# multiple_LED.net
KiCad netlist of a schematic drawn in EAGLE
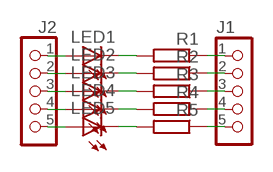
[diagram p0: schematic, sheet 1]

(export (version "E")
  (design (tool "Eeschema 10.0.6"))
  (components
    (comp (ref "J1")
      (value "CON_HEADER_1X05-PTH")
      (footprint "eagle-import:M1X5")
      (libsource (lib "eagle-import") (part "CON_HEADER_1X05-PTH"))
    )
    (comp (ref "J2")
      (value "CON_HEADER_1X05-PTH")
      (footprint "eagle-import:M1X5")
      (libsource (lib "eagle-import") (part "CON_HEADER_1X05-PTH"))
    )
    (comp (ref "LED1")
      (value "LED-0805")
      (footprint "eagle-import:LED-805")
      (libsource (lib "eagle-import") (part "LED-0805"))
    )
    (comp (ref "LED2")
      (value "LED-0805")
      (footprint "eagle-import:LED-805")
      (libsource (lib "eagle-import") (part "LED-0805"))
    )
    (comp (ref "LED3")
      (value "LED-0805")
      (footprint "eagle-import:LED-805")
      (libsource (lib "eagle-import") (part "LED-0805"))
    )
    (comp (ref "LED4")
      (value "LED-0805")
      (footprint "eagle-import:LED-805")
      (libsource (lib "eagle-import") (part "LED-0805"))
    )
    (comp (ref "LED5")
      (value "LED-0805")
      (footprint "eagle-import:LED-805")
      (libsource (lib "eagle-import") (part "LED-0805"))
    )
    (comp (ref "R1")
      (value "RESISTOR-0603")
      (footprint "eagle-import:R603")
      (libsource (lib "eagle-import") (part "RESISTOR-0603"))
    )
    (comp (ref "R2")
      (value "RESISTOR-0603")
      (footprint "eagle-import:R603")
      (libsource (lib "eagle-import") (part "RESISTOR-0603"))
    )
    (comp (ref "R3")
      (value "RESISTOR-0603")
      (footprint "eagle-import:R603")
      (libsource (lib "eagle-import") (part "RESISTOR-0603"))
    )
    (comp (ref "R4")
      (value "RESISTOR-0603")
      (footprint "eagle-import:R603")
      (libsource (lib "eagle-import") (part "RESISTOR-0603"))
    )
    (comp (ref "R5")
      (value "RESISTOR-0603")
      (footprint "eagle-import:R603")
      (libsource (lib "eagle-import") (part "RESISTOR-0603"))
    )
  )
  (nets
    (net (code "1") (name "Net-(J1-Pad1)") (class "Default")
      (node (ref "J1") (pin "1") (pinfunction "1_1") (pintype "bidirectional"))
      (node (ref "R1") (pin "1") (pinfunction "1_1") (pintype "passive"))
    )
    (net (code "2") (name "Net-(J1-Pad2)") (class "Default")
      (node (ref "J1") (pin "2") (pinfunction "2_2") (pintype "bidirectional"))
      (node (ref "R2") (pin "1") (pinfunction "1_1") (pintype "passive"))
    )
    (net (code "3") (name "Net-(J1-Pad3)") (class "Default")
      (node (ref "J1") (pin "3") (pinfunction "3_3") (pintype "bidirectional"))
      (node (ref "R3") (pin "1") (pinfunction "1_1") (pintype "passive"))
    )
    (net (code "4") (name "Net-(J1-Pad4)") (class "Default")
      (node (ref "J1") (pin "4") (pinfunction "4_4") (pintype "bidirectional"))
      (node (ref "R4") (pin "1") (pinfunction "1_1") (pintype "passive"))
    )
    (net (code "5") (name "Net-(J1-Pad5)") (class "Default")
      (node (ref "J1") (pin "5") (pinfunction "5_5") (pintype "bidirectional"))
      (node (ref "R5") (pin "1") (pinfunction "1_1") (pintype "passive"))
    )
    (net (code "6") (name "Net-(J2-Pad1)") (class "Default")
      (node (ref "J2") (pin "1") (pinfunction "1_1") (pintype "bidirectional"))
      (node (ref "LED1") (pin "A") (pinfunction "A_A") (pintype "passive"))
    )
    (net (code "7") (name "Net-(J2-Pad2)") (class "Default")
      (node (ref "J2") (pin "2") (pinfunction "2_2") (pintype "bidirectional"))
      (node (ref "LED2") (pin "A") (pinfunction "A_A") (pintype "passive"))
    )
    (net (code "8") (name "Net-(J2-Pad3)") (class "Default")
      (node (ref "J2") (pin "3") (pinfunction "3_3") (pintype "bidirectional"))
      (node (ref "LED3") (pin "A") (pinfunction "A_A") (pintype "passive"))
    )
    (net (code "9") (name "Net-(J2-Pad4)") (class "Default")
      (node (ref "J2") (pin "4") (pinfunction "4_4") (pintype "bidirectional"))
      (node (ref "LED4") (pin "A") (pinfunction "A_A") (pintype "passive"))
    )
    (net (code "10") (name "Net-(J2-Pad5)") (class "Default")
      (node (ref "J2") (pin "5") (pinfunction "5_5") (pintype "bidirectional"))
      (node (ref "LED5") (pin "A") (pinfunction "A_A") (pintype "passive"))
    )
    (net (code "11") (name "Net-(LED1-PadC)") (class "Default")
      (node (ref "LED1") (pin "C") (pinfunction "C_C") (pintype "passive"))
      (node (ref "R1") (pin "2") (pinfunction "2_2") (pintype "passive"))
    )
    (net (code "12") (name "Net-(LED2-PadC)") (class "Default")
      (node (ref "LED2") (pin "C") (pinfunction "C_C") (pintype "passive"))
      (node (ref "R2") (pin "2") (pinfunction "2_2") (pintype "passive"))
    )
    (net (code "13") (name "Net-(LED3-PadC)") (class "Default")
      (node (ref "LED3") (pin "C") (pinfunction "C_C") (pintype "passive"))
      (node (ref "R3") (pin "2") (pinfunction "2_2") (pintype "passive"))
    )
    (net (code "14") (name "Net-(LED4-PadC)") (class "Default")
      (node (ref "LED4") (pin "C") (pinfunction "C_C") (pintype "passive"))
      (node (ref "R4") (pin "2") (pinfunction "2_2") (pintype "passive"))
    )
    (net (code "15") (name "Net-(LED5-PadC)") (class "Default")
      (node (ref "LED5") (pin "C") (pinfunction "C_C") (pintype "passive"))
      (node (ref "R5") (pin "2") (pinfunction "2_2") (pintype "passive"))
    )
  )
)
